# CapArray.net
KiCad netlist of a schematic drawn in Altium Designer
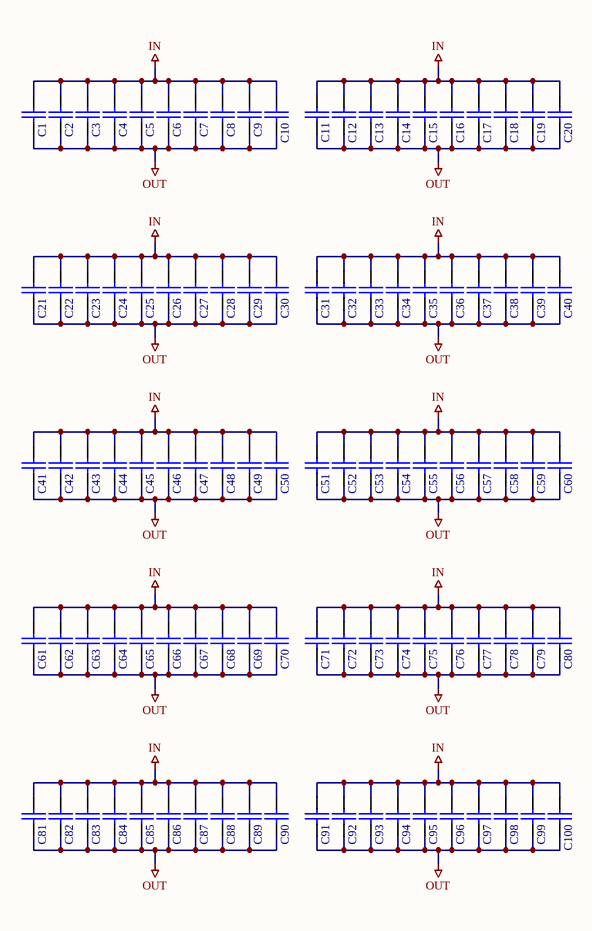
[diagram p0: CapArray.SchDoc]

(export (version "E")
  (design (tool "Eeschema 10.0.6"))
  (components
    (comp (ref "C1")
      (value "CAP")
      (footprint "1206C")
      (description "100uF,25V")
      (libsource (lib "MyLib") (part "CAP"))
    )
    (comp (ref "C2")
      (value "CAP")
      (footprint "1206C")
      (description "100uF,25V")
      (libsource (lib "MyLib") (part "CAP"))
    )
    (comp (ref "C3")
      (value "CAP")
      (footprint "1206C")
      (description "100uF,25V")
      (libsource (lib "MyLib") (part "CAP"))
    )
    (comp (ref "C4")
      (value "CAP")
      (footprint "1206C")
      (description "100uF,25V")
      (libsource (lib "MyLib") (part "CAP"))
    )
    (comp (ref "C5")
      (value "CAP")
      (footprint "1206C")
      (description "100uF,25V")
      (libsource (lib "MyLib") (part "CAP"))
    )
    (comp (ref "C6")
      (value "CAP")
      (footprint "1206C")
      (description "100uF,25V")
      (libsource (lib "MyLib") (part "CAP"))
    )
    (comp (ref "C7")
      (value "CAP")
      (footprint "1206C")
      (description "100uF,25V")
      (libsource (lib "MyLib") (part "CAP"))
    )
    (comp (ref "C8")
      (value "CAP")
      (footprint "1206C")
      (description "100uF,25V")
      (libsource (lib "MyLib") (part "CAP"))
    )
    (comp (ref "C9")
      (value "CAP")
      (footprint "1206C")
      (description "100uF,25V")
      (libsource (lib "MyLib") (part "CAP"))
    )
    (comp (ref "C10")
      (value "CAP")
      (footprint "1206C")
      (description "100uF,25V")
      (libsource (lib "MyLib") (part "CAP"))
    )
    (comp (ref "C11")
      (value "CAP")
      (footprint "1206C")
      (description "100uF,25V")
      (libsource (lib "MyLib") (part "CAP"))
    )
    (comp (ref "C12")
      (value "CAP")
      (footprint "1206C")
      (description "100uF,25V")
      (libsource (lib "MyLib") (part "CAP"))
    )
    (comp (ref "C13")
      (value "CAP")
      (footprint "1206C")
      (description "100uF,25V")
      (libsource (lib "MyLib") (part "CAP"))
    )
    (comp (ref "C14")
      (value "CAP")
      (footprint "1206C")
      (description "100uF,25V")
      (libsource (lib "MyLib") (part "CAP"))
    )
    (comp (ref "C15")
      (value "CAP")
      (footprint "1206C")
      (description "100uF,25V")
      (libsource (lib "MyLib") (part "CAP"))
    )
    (comp (ref "C16")
      (value "CAP")
      (footprint "1206C")
      (description "100uF,25V")
      (libsource (lib "MyLib") (part "CAP"))
    )
    (comp (ref "C17")
      (value "CAP")
      (footprint "1206C")
      (description "100uF,25V")
      (libsource (lib "MyLib") (part "CAP"))
    )
    (comp (ref "C18")
      (value "CAP")
      (footprint "1206C")
      (description "100uF,25V")
      (libsource (lib "MyLib") (part "CAP"))
    )
    (comp (ref "C19")
      (value "CAP")
      (footprint "1206C")
      (description "100uF,25V")
      (libsource (lib "MyLib") (part "CAP"))
    )
    (comp (ref "C20")
      (value "CAP")
      (footprint "1206C")
      (description "100uF,25V")
      (libsource (lib "MyLib") (part "CAP"))
    )
    (comp (ref "C21")
      (value "CAP")
      (footprint "1206C")
      (description "100uF,25V")
      (libsource (lib "MyLib") (part "CAP"))
    )
    (comp (ref "C22")
      (value "CAP")
      (footprint "1206C")
      (description "100uF,25V")
      (libsource (lib "MyLib") (part "CAP"))
    )
    (comp (ref "C23")
      (value "CAP")
      (footprint "1206C")
      (description "100uF,25V")
      (libsource (lib "MyLib") (part "CAP"))
    )
    (comp (ref "C24")
      (value "CAP")
      (footprint "1206C")
      (description "100uF,25V")
      (libsource (lib "MyLib") (part "CAP"))
    )
    (comp (ref "C25")
      (value "CAP")
      (footprint "1206C")
      (description "100uF,25V")
      (libsource (lib "MyLib") (part "CAP"))
    )
    (comp (ref "C26")
      (value "CAP")
      (footprint "1206C")
      (description "100uF,25V")
      (libsource (lib "MyLib") (part "CAP"))
    )
    (comp (ref "C27")
      (value "CAP")
      (footprint "1206C")
      (description "100uF,25V")
      (libsource (lib "MyLib") (part "CAP"))
    )
    (comp (ref "C28")
      (value "CAP")
      (footprint "1206C")
      (description "100uF,25V")
      (libsource (lib "MyLib") (part "CAP"))
    )
    (comp (ref "C29")
      (value "CAP")
      (footprint "1206C")
      (description "100uF,25V")
      (libsource (lib "MyLib") (part "CAP"))
    )
    (comp (ref "C30")
      (value "CAP")
      (footprint "1206C")
      (description "100uF,25V")
      (libsource (lib "MyLib") (part "CAP"))
    )
    (comp (ref "C31")
      (value "CAP")
      (footprint "1206C")
      (description "100uF,25V")
      (libsource (lib "MyLib") (part "CAP"))
    )
    (comp (ref "C32")
      (value "CAP")
      (footprint "1206C")
      (description "100uF,25V")
      (libsource (lib "MyLib") (part "CAP"))
    )
    (comp (ref "C33")
      (value "CAP")
      (footprint "1206C")
      (description "100uF,25V")
      (libsource (lib "MyLib") (part "CAP"))
    )
    (comp (ref "C34")
      (value "CAP")
      (footprint "1206C")
      (description "100uF,25V")
      (libsource (lib "MyLib") (part "CAP"))
    )
    (comp (ref "C35")
      (value "CAP")
      (footprint "1206C")
      (description "100uF,25V")
      (libsource (lib "MyLib") (part "CAP"))
    )
    (comp (ref "C36")
      (value "CAP")
      (footprint "1206C")
      (description "100uF,25V")
      (libsource (lib "MyLib") (part "CAP"))
    )
    (comp (ref "C37")
      (value "CAP")
      (footprint "1206C")
      (description "100uF,25V")
      (libsource (lib "MyLib") (part "CAP"))
    )
    (comp (ref "C38")
      (value "CAP")
      (footprint "1206C")
      (description "100uF,25V")
      (libsource (lib "MyLib") (part "CAP"))
    )
    (comp (ref "C39")
      (value "CAP")
      (footprint "1206C")
      (description "100uF,25V")
      (libsource (lib "MyLib") (part "CAP"))
    )
    (comp (ref "C40")
      (value "CAP")
      (footprint "1206C")
      (description "100uF,25V")
      (libsource (lib "MyLib") (part "CAP"))
    )
    (comp (ref "C41")
      (value "CAP")
      (footprint "1206C")
      (description "100uF,25V")
      (libsource (lib "MyLib") (part "CAP"))
    )
    (comp (ref "C42")
      (value "CAP")
      (footprint "1206C")
      (description "100uF,25V")
      (libsource (lib "MyLib") (part "CAP"))
    )
    (comp (ref "C43")
      (value "CAP")
      (footprint "1206C")
      (description "100uF,25V")
      (libsource (lib "MyLib") (part "CAP"))
    )
    (comp (ref "C44")
      (value "CAP")
      (footprint "1206C")
      (description "100uF,25V")
      (libsource (lib "MyLib") (part "CAP"))
    )
    (comp (ref "C45")
      (value "CAP")
      (footprint "1206C")
      (description "100uF,25V")
      (libsource (lib "MyLib") (part "CAP"))
    )
    (comp (ref "C46")
      (value "CAP")
      (footprint "1206C")
      (description "100uF,25V")
      (libsource (lib "MyLib") (part "CAP"))
    )
    (comp (ref "C47")
      (value "CAP")
      (footprint "1206C")
      (description "100uF,25V")
      (libsource (lib "MyLib") (part "CAP"))
    )
    (comp (ref "C48")
      (value "CAP")
      (footprint "1206C")
      (description "100uF,25V")
      (libsource (lib "MyLib") (part "CAP"))
    )
    (comp (ref "C49")
      (value "CAP")
      (footprint "1206C")
      (description "100uF,25V")
      (libsource (lib "MyLib") (part "CAP"))
    )
    (comp (ref "C50")
      (value "CAP")
      (footprint "1206C")
      (description "100uF,25V")
      (libsource (lib "MyLib") (part "CAP"))
    )
    (comp (ref "C51")
      (value "CAP")
      (footprint "1206C")
      (description "100uF,25V")
      (libsource (lib "MyLib") (part "CAP"))
    )
    (comp (ref "C52")
      (value "CAP")
      (footprint "1206C")
      (description "100uF,25V")
      (libsource (lib "MyLib") (part "CAP"))
    )
    (comp (ref "C53")
      (value "CAP")
      (footprint "1206C")
      (description "100uF,25V")
      (libsource (lib "MyLib") (part "CAP"))
    )
    (comp (ref "C54")
      (value "CAP")
      (footprint "1206C")
      (description "100uF,25V")
      (libsource (lib "MyLib") (part "CAP"))
    )
    (comp (ref "C55")
      (value "CAP")
      (footprint "1206C")
      (description "100uF,25V")
      (libsource (lib "MyLib") (part "CAP"))
    )
    (comp (ref "C56")
      (value "CAP")
      (footprint "1206C")
      (description "100uF,25V")
      (libsource (lib "MyLib") (part "CAP"))
    )
    (comp (ref "C57")
      (value "CAP")
      (footprint "1206C")
      (description "100uF,25V")
      (libsource (lib "MyLib") (part "CAP"))
    )
    (comp (ref "C58")
      (value "CAP")
      (footprint "1206C")
      (description "100uF,25V")
      (libsource (lib "MyLib") (part "CAP"))
    )
    (comp (ref "C59")
      (value "CAP")
      (footprint "1206C")
      (description "100uF,25V")
      (libsource (lib "MyLib") (part "CAP"))
    )
    (comp (ref "C60")
      (value "CAP")
      (footprint "1206C")
      (description "100uF,25V")
      (libsource (lib "MyLib") (part "CAP"))
    )
    (comp (ref "C61")
      (value "CAP")
      (footprint "1206C")
      (description "100uF,25V")
      (libsource (lib "MyLib") (part "CAP"))
    )
    (comp (ref "C62")
      (value "CAP")
      (footprint "1206C")
      (description "100uF,25V")
      (libsource (lib "MyLib") (part "CAP"))
    )
    (comp (ref "C63")
      (value "CAP")
      (footprint "1206C")
      (description "100uF,25V")
      (libsource (lib "MyLib") (part "CAP"))
    )
    (comp (ref "C64")
      (value "CAP")
      (footprint "1206C")
      (description "100uF,25V")
      (libsource (lib "MyLib") (part "CAP"))
    )
    (comp (ref "C65")
      (value "CAP")
      (footprint "1206C")
      (description "100uF,25V")
      (libsource (lib "MyLib") (part "CAP"))
    )
    (comp (ref "C66")
      (value "CAP")
      (footprint "1206C")
      (description "100uF,25V")
      (libsource (lib "MyLib") (part "CAP"))
    )
    (comp (ref "C67")
      (value "CAP")
      (footprint "1206C")
      (description "100uF,25V")
      (libsource (lib "MyLib") (part "CAP"))
    )
    (comp (ref "C68")
      (value "CAP")
      (footprint "1206C")
      (description "100uF,25V")
      (libsource (lib "MyLib") (part "CAP"))
    )
    (comp (ref "C69")
      (value "CAP")
      (footprint "1206C")
      (description "100uF,25V")
      (libsource (lib "MyLib") (part "CAP"))
    )
    (comp (ref "C70")
      (value "CAP")
      (footprint "1206C")
      (description "100uF,25V")
      (libsource (lib "MyLib") (part "CAP"))
    )
    (comp (ref "C71")
      (value "CAP")
      (footprint "1206C")
      (description "100uF,25V")
      (libsource (lib "MyLib") (part "CAP"))
    )
    (comp (ref "C72")
      (value "CAP")
      (footprint "1206C")
      (description "100uF,25V")
      (libsource (lib "MyLib") (part "CAP"))
    )
    (comp (ref "C73")
      (value "CAP")
      (footprint "1206C")
      (description "100uF,25V")
      (libsource (lib "MyLib") (part "CAP"))
    )
    (comp (ref "C74")
      (value "CAP")
      (footprint "1206C")
      (description "100uF,25V")
      (libsource (lib "MyLib") (part "CAP"))
    )
    (comp (ref "C75")
      (value "CAP")
      (footprint "1206C")
      (description "100uF,25V")
      (libsource (lib "MyLib") (part "CAP"))
    )
    (comp (ref "C76")
      (value "CAP")
      (footprint "1206C")
      (description "100uF,25V")
      (libsource (lib "MyLib") (part "CAP"))
    )
    (comp (ref "C77")
      (value "CAP")
      (footprint "1206C")
      (description "100uF,25V")
      (libsource (lib "MyLib") (part "CAP"))
    )
    (comp (ref "C78")
      (value "CAP")
      (footprint "1206C")
      (description "100uF,25V")
      (libsource (lib "MyLib") (part "CAP"))
    )
    (comp (ref "C79")
      (value "CAP")
      (footprint "1206C")
      (description "100uF,25V")
      (libsource (lib "MyLib") (part "CAP"))
    )
    (comp (ref "C80")
      (value "CAP")
      (footprint "1206C")
      (description "100uF,25V")
      (libsource (lib "MyLib") (part "CAP"))
    )
    (comp (ref "C81")
      (value "CAP")
      (footprint "1206C")
      (description "100uF,25V")
      (libsource (lib "MyLib") (part "CAP"))
    )
    (comp (ref "C82")
      (value "CAP")
      (footprint "1206C")
      (description "100uF,25V")
      (libsource (lib "MyLib") (part "CAP"))
    )
    (comp (ref "C83")
      (value "CAP")
      (footprint "1206C")
      (description "100uF,25V")
      (libsource (lib "MyLib") (part "CAP"))
    )
    (comp (ref "C84")
      (value "CAP")
      (footprint "1206C")
      (description "100uF,25V")
      (libsource (lib "MyLib") (part "CAP"))
    )
    (comp (ref "C85")
      (value "CAP")
      (footprint "1206C")
      (description "100uF,25V")
      (libsource (lib "MyLib") (part "CAP"))
    )
    (comp (ref "C86")
      (value "CAP")
      (footprint "1206C")
      (description "100uF,25V")
      (libsource (lib "MyLib") (part "CAP"))
    )
    (comp (ref "C87")
      (value "CAP")
      (footprint "1206C")
      (description "100uF,25V")
      (libsource (lib "MyLib") (part "CAP"))
    )
    (comp (ref "C88")
      (value "CAP")
      (footprint "1206C")
      (description "100uF,25V")
      (libsource (lib "MyLib") (part "CAP"))
    )
    (comp (ref "C89")
      (value "CAP")
      (footprint "1206C")
      (description "100uF,25V")
      (libsource (lib "MyLib") (part "CAP"))
    )
    (comp (ref "C90")
      (value "CAP")
      (footprint "1206C")
      (description "100uF,25V")
      (libsource (lib "MyLib") (part "CAP"))
    )
    (comp (ref "C91")
      (value "CAP")
      (footprint "1206C")
      (description "100uF,25V")
      (libsource (lib "MyLib") (part "CAP"))
    )
    (comp (ref "C92")
      (value "CAP")
      (footprint "1206C")
      (description "100uF,25V")
      (libsource (lib "MyLib") (part "CAP"))
    )
    (comp (ref "C93")
      (value "CAP")
      (footprint "1206C")
      (description "100uF,25V")
      (libsource (lib "MyLib") (part "CAP"))
    )
    (comp (ref "C94")
      (value "CAP")
      (footprint "1206C")
      (description "100uF,25V")
      (libsource (lib "MyLib") (part "CAP"))
    )
    (comp (ref "C95")
      (value "CAP")
      (footprint "1206C")
      (description "100uF,25V")
      (libsource (lib "MyLib") (part "CAP"))
    )
    (comp (ref "C96")
      (value "CAP")
      (footprint "1206C")
      (description "100uF,25V")
      (libsource (lib "MyLib") (part "CAP"))
    )
    (comp (ref "C97")
      (value "CAP")
      (footprint "1206C")
      (description "100uF,25V")
      (libsource (lib "MyLib") (part "CAP"))
    )
    (comp (ref "C98")
      (value "CAP")
      (footprint "1206C")
      (description "100uF,25V")
      (libsource (lib "MyLib") (part "CAP"))
    )
    (comp (ref "C99")
      (value "CAP")
      (footprint "1206C")
      (description "100uF,25V")
      (libsource (lib "MyLib") (part "CAP"))
    )
    (comp (ref "C100")
      (value "CAP")
      (footprint "1206C")
      (description "100uF,25V")
      (libsource (lib "MyLib") (part "CAP"))
    )
  )
  (nets
    (net (code "1") (name "IN") (class "Default")
      (node (ref "C1") (pin "1") (pinfunction "1_1") (pintype "passive"))
      (node (ref "C10") (pin "1") (pinfunction "1_1") (pintype "passive"))
      (node (ref "C100") (pin "1") (pinfunction "1_1") (pintype "passive"))
      (node (ref "C11") (pin "1") (pinfunction "1_1") (pintype "passive"))
      (node (ref "C12") (pin "1") (pinfunction "1_1") (pintype "passive"))
      (node (ref "C13") (pin "1") (pinfunction "1_1") (pintype "passive"))
      (node (ref "C14") (pin "1") (pinfunction "1_1") (pintype "passive"))
      (node (ref "C15") (pin "1") (pinfunction "1_1") (pintype "passive"))
      (node (ref "C16") (pin "1") (pinfunction "1_1") (pintype "passive"))
      (node (ref "C17") (pin "1") (pinfunction "1_1") (pintype "passive"))
      (node (ref "C18") (pin "1") (pinfunction "1_1") (pintype "passive"))
      (node (ref "C19") (pin "1") (pinfunction "1_1") (pintype "passive"))
      (node (ref "C2") (pin "1") (pinfunction "1_1") (pintype "passive"))
      (node (ref "C20") (pin "1") (pinfunction "1_1") (pintype "passive"))
      (node (ref "C21") (pin "1") (pinfunction "1_1") (pintype "passive"))
      (node (ref "C22") (pin "1") (pinfunction "1_1") (pintype "passive"))
      (node (ref "C23") (pin "1") (pinfunction "1_1") (pintype "passive"))
      (node (ref "C24") (pin "1") (pinfunction "1_1") (pintype "passive"))
      (node (ref "C25") (pin "1") (pinfunction "1_1") (pintype "passive"))
      (node (ref "C26") (pin "1") (pinfunction "1_1") (pintype "passive"))
      (node (ref "C27") (pin "1") (pinfunction "1_1") (pintype "passive"))
      (node (ref "C28") (pin "1") (pinfunction "1_1") (pintype "passive"))
      (node (ref "C29") (pin "1") (pinfunction "1_1") (pintype "passive"))
      (node (ref "C3") (pin "1") (pinfunction "1_1") (pintype "passive"))
      (node (ref "C30") (pin "1") (pinfunction "1_1") (pintype "passive"))
      (node (ref "C31") (pin "1") (pinfunction "1_1") (pintype "passive"))
      (node (ref "C32") (pin "1") (pinfunction "1_1") (pintype "passive"))
      (node (ref "C33") (pin "1") (pinfunction "1_1") (pintype "passive"))
      (node (ref "C34") (pin "1") (pinfunction "1_1") (pintype "passive"))
      (node (ref "C35") (pin "1") (pinfunction "1_1") (pintype "passive"))
      (node (ref "C36") (pin "1") (pinfunction "1_1") (pintype "passive"))
      (node (ref "C37") (pin "1") (pinfunction "1_1") (pintype "passive"))
      (node (ref "C38") (pin "1") (pinfunction "1_1") (pintype "passive"))
      (node (ref "C39") (pin "1") (pinfunction "1_1") (pintype "passive"))
      (node (ref "C4") (pin "1") (pinfunction "1_1") (pintype "passive"))
      (node (ref "C40") (pin "1") (pinfunction "1_1") (pintype "passive"))
      (node (ref "C41") (pin "1") (pinfunction "1_1") (pintype "passive"))
      (node (ref "C42") (pin "1") (pinfunction "1_1") (pintype "passive"))
      (node (ref "C43") (pin "1") (pinfunction "1_1") (pintype "passive"))
      (node (ref "C44") (pin "1") (pinfunction "1_1") (pintype "passive"))
      (node (ref "C45") (pin "1") (pinfunction "1_1") (pintype "passive"))
      (node (ref "C46") (pin "1") (pinfunction "1_1") (pintype "passive"))
      (node (ref "C47") (pin "1") (pinfunction "1_1") (pintype "passive"))
      (node (ref "C48") (pin "1") (pinfunction "1_1") (pintype "passive"))
      (node (ref "C49") (pin "1") (pinfunction "1_1") (pintype "passive"))
      (node (ref "C5") (pin "1") (pinfunction "1_1") (pintype "passive"))
      (node (ref "C50") (pin "1") (pinfunction "1_1") (pintype "passive"))
      (node (ref "C51") (pin "1") (pinfunction "1_1") (pintype "passive"))
      (node (ref "C52") (pin "1") (pinfunction "1_1") (pintype "passive"))
      (node (ref "C53") (pin "1") (pinfunction "1_1") (pintype "passive"))
      (node (ref "C54") (pin "1") (pinfunction "1_1") (pintype "passive"))
      (node (ref "C55") (pin "1") (pinfunction "1_1") (pintype "passive"))
      (node (ref "C56") (pin "1") (pinfunction "1_1") (pintype "passive"))
      (node (ref "C57") (pin "1") (pinfunction "1_1") (pintype "passive"))
      (node (ref "C58") (pin "1") (pinfunction "1_1") (pintype "passive"))
      (node (ref "C59") (pin "1") (pinfunction "1_1") (pintype "passive"))
      (node (ref "C6") (pin "1") (pinfunction "1_1") (pintype "passive"))
      (node (ref "C60") (pin "1") (pinfunction "1_1") (pintype "passive"))
      (node (ref "C61") (pin "1") (pinfunction "1_1") (pintype "passive"))
      (node (ref "C62") (pin "1") (pinfunction "1_1") (pintype "passive"))
      (node (ref "C63") (pin "1") (pinfunction "1_1") (pintype "passive"))
      (node (ref "C64") (pin "1") (pinfunction "1_1") (pintype "passive"))
      (node (ref "C65") (pin "1") (pinfunction "1_1") (pintype "passive"))
      (node (ref "C66") (pin "1") (pinfunction "1_1") (pintype "passive"))
      (node (ref "C67") (pin "1") (pinfunction "1_1") (pintype "passive"))
      (node (ref "C68") (pin "1") (pinfunction "1_1") (pintype "passive"))
      (node (ref "C69") (pin "1") (pinfunction "1_1") (pintype "passive"))
      (node (ref "C7") (pin "1") (pinfunction "1_1") (pintype "passive"))
      (node (ref "C70") (pin "1") (pinfunction "1_1") (pintype "passive"))
      (node (ref "C71") (pin "1") (pinfunction "1_1") (pintype "passive"))
      (node (ref "C72") (pin "1") (pinfunction "1_1") (pintype "passive"))
      (node (ref "C73") (pin "1") (pinfunction "1_1") (pintype "passive"))
      (node (ref "C74") (pin "1") (pinfunction "1_1") (pintype "passive"))
      (node (ref "C75") (pin "1") (pinfunction "1_1") (pintype "passive"))
      (node (ref "C76") (pin "1") (pinfunction "1_1") (pintype "passive"))
      (node (ref "C77") (pin "1") (pinfunction "1_1") (pintype "passive"))
      (node (ref "C78") (pin "1") (pinfunction "1_1") (pintype "passive"))
      (node (ref "C79") (pin "1") (pinfunction "1_1") (pintype "passive"))
      (node (ref "C8") (pin "1") (pinfunction "1_1") (pintype "passive"))
      (node (ref "C80") (pin "1") (pinfunction "1_1") (pintype "passive"))
      (node (ref "C81") (pin "1") (pinfunction "1_1") (pintype "passive"))
      (node (ref "C82") (pin "1") (pinfunction "1_1") (pintype "passive"))
      (node (ref "C83") (pin "1") (pinfunction "1_1") (pintype "passive"))
      (node (ref "C84") (pin "1") (pinfunction "1_1") (pintype "passive"))
      (node (ref "C85") (pin "1") (pinfunction "1_1") (pintype "passive"))
      (node (ref "C86") (pin "1") (pinfunction "1_1") (pintype "passive"))
      (node (ref "C87") (pin "1") (pinfunction "1_1") (pintype "passive"))
      (node (ref "C88") (pin "1") (pinfunction "1_1") (pintype "passive"))
      (node (ref "C89") (pin "1") (pinfunction "1_1") (pintype "passive"))
      (node (ref "C9") (pin "1") (pinfunction "1_1") (pintype "passive"))
      (node (ref "C90") (pin "1") (pinfunction "1_1") (pintype "passive"))
      (node (ref "C91") (pin "1") (pinfunction "1_1") (pintype "passive"))
      (node (ref "C92") (pin "1") (pinfunction "1_1") (pintype "passive"))
      (node (ref "C93") (pin "1") (pinfunction "1_1") (pintype "passive"))
      (node (ref "C94") (pin "1") (pinfunction "1_1") (pintype "passive"))
      (node (ref "C95") (pin "1") (pinfunction "1_1") (pintype "passive"))
      (node (ref "C96") (pin "1") (pinfunction "1_1") (pintype "passive"))
      (node (ref "C97") (pin "1") (pinfunction "1_1") (pintype "passive"))
      (node (ref "C98") (pin "1") (pinfunction "1_1") (pintype "passive"))
      (node (ref "C99") (pin "1") (pinfunction "1_1") (pintype "passive"))
    )
    (net (code "2") (name "OUT") (class "Default")
      (node (ref "C1") (pin "2") (pinfunction "2_2") (pintype "passive"))
      (node (ref "C10") (pin "2") (pinfunction "2_2") (pintype "passive"))
      (node (ref "C100") (pin "2") (pinfunction "2_2") (pintype "passive"))
      (node (ref "C11") (pin "2") (pinfunction "2_2") (pintype "passive"))
      (node (ref "C12") (pin "2") (pinfunction "2_2") (pintype "passive"))
      (node (ref "C13") (pin "2") (pinfunction "2_2") (pintype "passive"))
      (node (ref "C14") (pin "2") (pinfunction "2_2") (pintype "passive"))
      (node (ref "C15") (pin "2") (pinfunction "2_2") (pintype "passive"))
      (node (ref "C16") (pin "2") (pinfunction "2_2") (pintype "passive"))
      (node (ref "C17") (pin "2") (pinfunction "2_2") (pintype "passive"))
      (node (ref "C18") (pin "2") (pinfunction "2_2") (pintype "passive"))
      (node (ref "C19") (pin "2") (pinfunction "2_2") (pintype "passive"))
      (node (ref "C2") (pin "2") (pinfunction "2_2") (pintype "passive"))
      (node (ref "C20") (pin "2") (pinfunction "2_2") (pintype "passive"))
      (node (ref "C21") (pin "2") (pinfunction "2_2") (pintype "passive"))
      (node (ref "C22") (pin "2") (pinfunction "2_2") (pintype "passive"))
      (node (ref "C23") (pin "2") (pinfunction "2_2") (pintype "passive"))
      (node (ref "C24") (pin "2") (pinfunction "2_2") (pintype "passive"))
      (node (ref "C25") (pin "2") (pinfunction "2_2") (pintype "passive"))
      (node (ref "C26") (pin "2") (pinfunction "2_2") (pintype "passive"))
      (node (ref "C27") (pin "2") (pinfunction "2_2") (pintype "passive"))
      (node (ref "C28") (pin "2") (pinfunction "2_2") (pintype "passive"))
      (node (ref "C29") (pin "2") (pinfunction "2_2") (pintype "passive"))
      (node (ref "C3") (pin "2") (pinfunction "2_2") (pintype "passive"))
      (node (ref "C30") (pin "2") (pinfunction "2_2") (pintype "passive"))
      (node (ref "C31") (pin "2") (pinfunction "2_2") (pintype "passive"))
      (node (ref "C32") (pin "2") (pinfunction "2_2") (pintype "passive"))
      (node (ref "C33") (pin "2") (pinfunction "2_2") (pintype "passive"))
      (node (ref "C34") (pin "2") (pinfunction "2_2") (pintype "passive"))
      (node (ref "C35") (pin "2") (pinfunction "2_2") (pintype "passive"))
      (node (ref "C36") (pin "2") (pinfunction "2_2") (pintype "passive"))
      (node (ref "C37") (pin "2") (pinfunction "2_2") (pintype "passive"))
      (node (ref "C38") (pin "2") (pinfunction "2_2") (pintype "passive"))
      (node (ref "C39") (pin "2") (pinfunction "2_2") (pintype "passive"))
      (node (ref "C4") (pin "2") (pinfunction "2_2") (pintype "passive"))
      (node (ref "C40") (pin "2") (pinfunction "2_2") (pintype "passive"))
      (node (ref "C41") (pin "2") (pinfunction "2_2") (pintype "passive"))
      (node (ref "C42") (pin "2") (pinfunction "2_2") (pintype "passive"))
      (node (ref "C43") (pin "2") (pinfunction "2_2") (pintype "passive"))
      (node (ref "C44") (pin "2") (pinfunction "2_2") (pintype "passive"))
      (node (ref "C45") (pin "2") (pinfunction "2_2") (pintype "passive"))
      (node (ref "C46") (pin "2") (pinfunction "2_2") (pintype "passive"))
      (node (ref "C47") (pin "2") (pinfunction "2_2") (pintype "passive"))
      (node (ref "C48") (pin "2") (pinfunction "2_2") (pintype "passive"))
      (node (ref "C49") (pin "2") (pinfunction "2_2") (pintype "passive"))
      (node (ref "C5") (pin "2") (pinfunction "2_2") (pintype "passive"))
      (node (ref "C50") (pin "2") (pinfunction "2_2") (pintype "passive"))
      (node (ref "C51") (pin "2") (pinfunction "2_2") (pintype "passive"))
      (node (ref "C52") (pin "2") (pinfunction "2_2") (pintype "passive"))
      (node (ref "C53") (pin "2") (pinfunction "2_2") (pintype "passive"))
      (node (ref "C54") (pin "2") (pinfunction "2_2") (pintype "passive"))
      (node (ref "C55") (pin "2") (pinfunction "2_2") (pintype "passive"))
      (node (ref "C56") (pin "2") (pinfunction "2_2") (pintype "passive"))
      (node (ref "C57") (pin "2") (pinfunction "2_2") (pintype "passive"))
      (node (ref "C58") (pin "2") (pinfunction "2_2") (pintype "passive"))
      (node (ref "C59") (pin "2") (pinfunction "2_2") (pintype "passive"))
      (node (ref "C6") (pin "2") (pinfunction "2_2") (pintype "passive"))
      (node (ref "C60") (pin "2") (pinfunction "2_2") (pintype "passive"))
      (node (ref "C61") (pin "2") (pinfunction "2_2") (pintype "passive"))
      (node (ref "C62") (pin "2") (pinfunction "2_2") (pintype "passive"))
      (node (ref "C63") (pin "2") (pinfunction "2_2") (pintype "passive"))
      (node (ref "C64") (pin "2") (pinfunction "2_2") (pintype "passive"))
      (node (ref "C65") (pin "2") (pinfunction "2_2") (pintype "passive"))
      (node (ref "C66") (pin "2") (pinfunction "2_2") (pintype "passive"))
      (node (ref "C67") (pin "2") (pinfunction "2_2") (pintype "passive"))
      (node (ref "C68") (pin "2") (pinfunction "2_2") (pintype "passive"))
      (node (ref "C69") (pin "2") (pinfunction "2_2") (pintype "passive"))
      (node (ref "C7") (pin "2") (pinfunction "2_2") (pintype "passive"))
      (node (ref "C70") (pin "2") (pinfunction "2_2") (pintype "passive"))
      (node (ref "C71") (pin "2") (pinfunction "2_2") (pintype "passive"))
      (node (ref "C72") (pin "2") (pinfunction "2_2") (pintype "passive"))
      (node (ref "C73") (pin "2") (pinfunction "2_2") (pintype "passive"))
      (node (ref "C74") (pin "2") (pinfunction "2_2") (pintype "passive"))
      (node (ref "C75") (pin "2") (pinfunction "2_2") (pintype "passive"))
      (node (ref "C76") (pin "2") (pinfunction "2_2") (pintype "passive"))
      (node (ref "C77") (pin "2") (pinfunction "2_2") (pintype "passive"))
      (node (ref "C78") (pin "2") (pinfunction "2_2") (pintype "passive"))
      (node (ref "C79") (pin "2") (pinfunction "2_2") (pintype "passive"))
      (node (ref "C8") (pin "2") (pinfunction "2_2") (pintype "passive"))
      (node (ref "C80") (pin "2") (pinfunction "2_2") (pintype "passive"))
      (node (ref "C81") (pin "2") (pinfunction "2_2") (pintype "passive"))
      (node (ref "C82") (pin "2") (pinfunction "2_2") (pintype "passive"))
      (node (ref "C83") (pin "2") (pinfunction "2_2") (pintype "passive"))
      (node (ref "C84") (pin "2") (pinfunction "2_2") (pintype "passive"))
      (node (ref "C85") (pin "2") (pinfunction "2_2") (pintype "passive"))
      (node (ref "C86") (pin "2") (pinfunction "2_2") (pintype "passive"))
      (node (ref "C87") (pin "2") (pinfunction "2_2") (pintype "passive"))
      (node (ref "C88") (pin "2") (pinfunction "2_2") (pintype "passive"))
      (node (ref "C89") (pin "2") (pinfunction "2_2") (pintype "passive"))
      (node (ref "C9") (pin "2") (pinfunction "2_2") (pintype "passive"))
      (node (ref "C90") (pin "2") (pinfunction "2_2") (pintype "passive"))
      (node (ref "C91") (pin "2") (pinfunction "2_2") (pintype "passive"))
      (node (ref "C92") (pin "2") (pinfunction "2_2") (pintype "passive"))
      (node (ref "C93") (pin "2") (pinfunction "2_2") (pintype "passive"))
      (node (ref "C94") (pin "2") (pinfunction "2_2") (pintype "passive"))
      (node (ref "C95") (pin "2") (pinfunction "2_2") (pintype "passive"))
      (node (ref "C96") (pin "2") (pinfunction "2_2") (pintype "passive"))
      (node (ref "C97") (pin "2") (pinfunction "2_2") (pintype "passive"))
      (node (ref "C98") (pin "2") (pinfunction "2_2") (pintype "passive"))
      (node (ref "C99") (pin "2") (pinfunction "2_2") (pintype "passive"))
    )
  )
)
